# Top_Level.net
KiCad netlist of a schematic drawn in Altium Designer
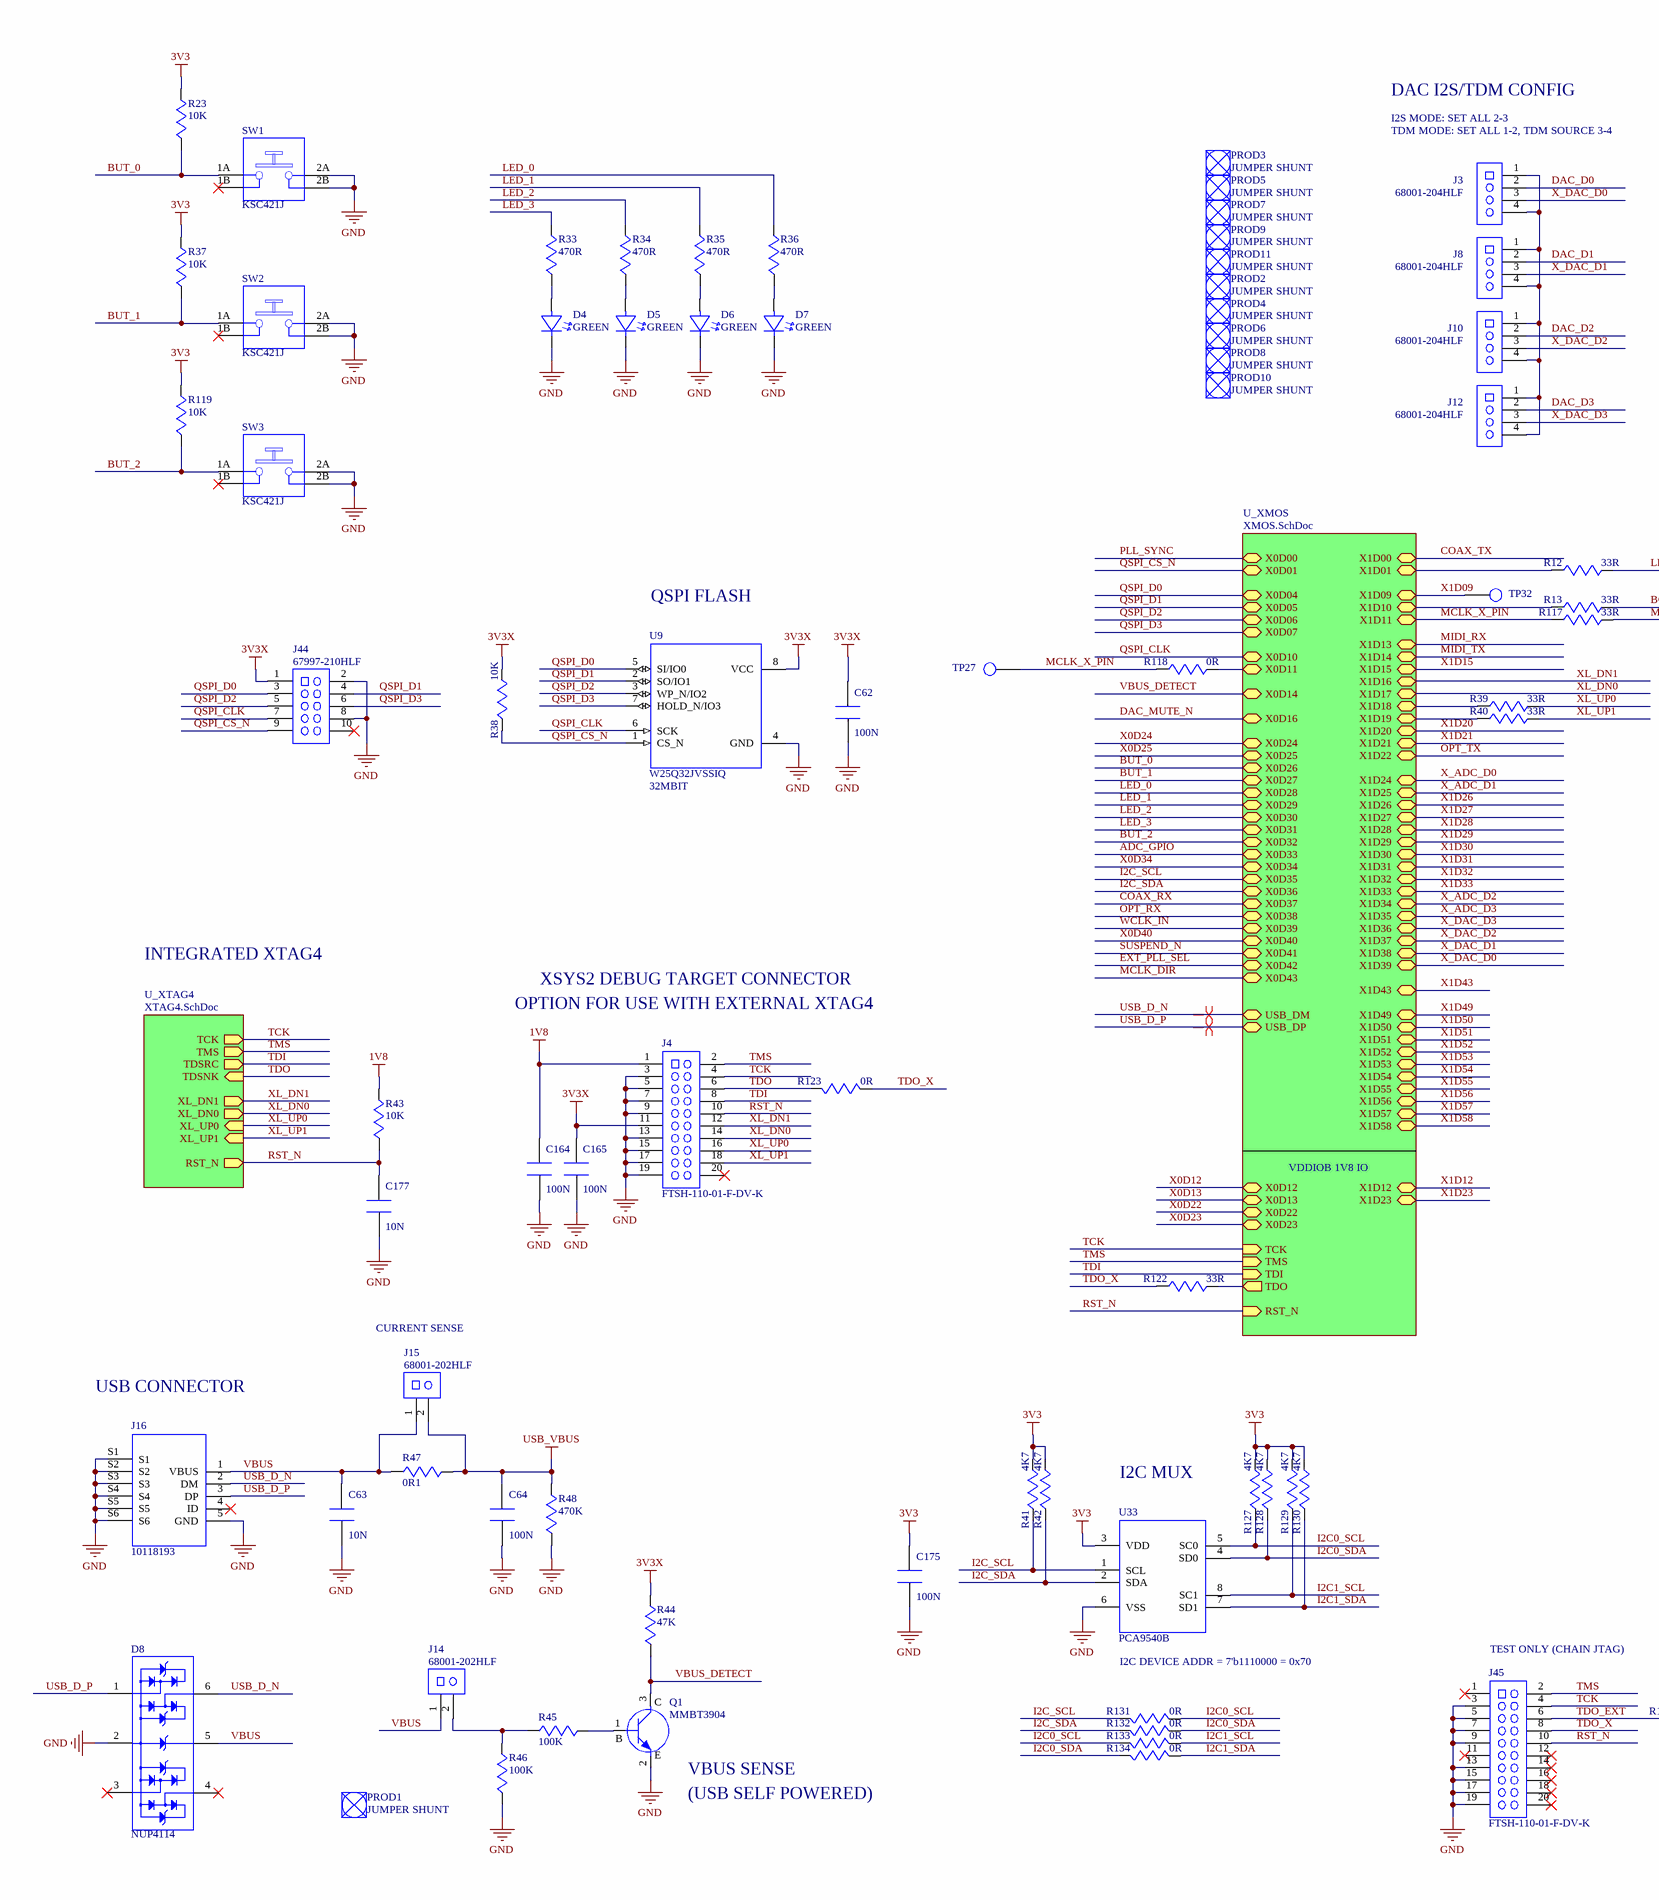
[diagram p0: Top Level.SchDoc, left]
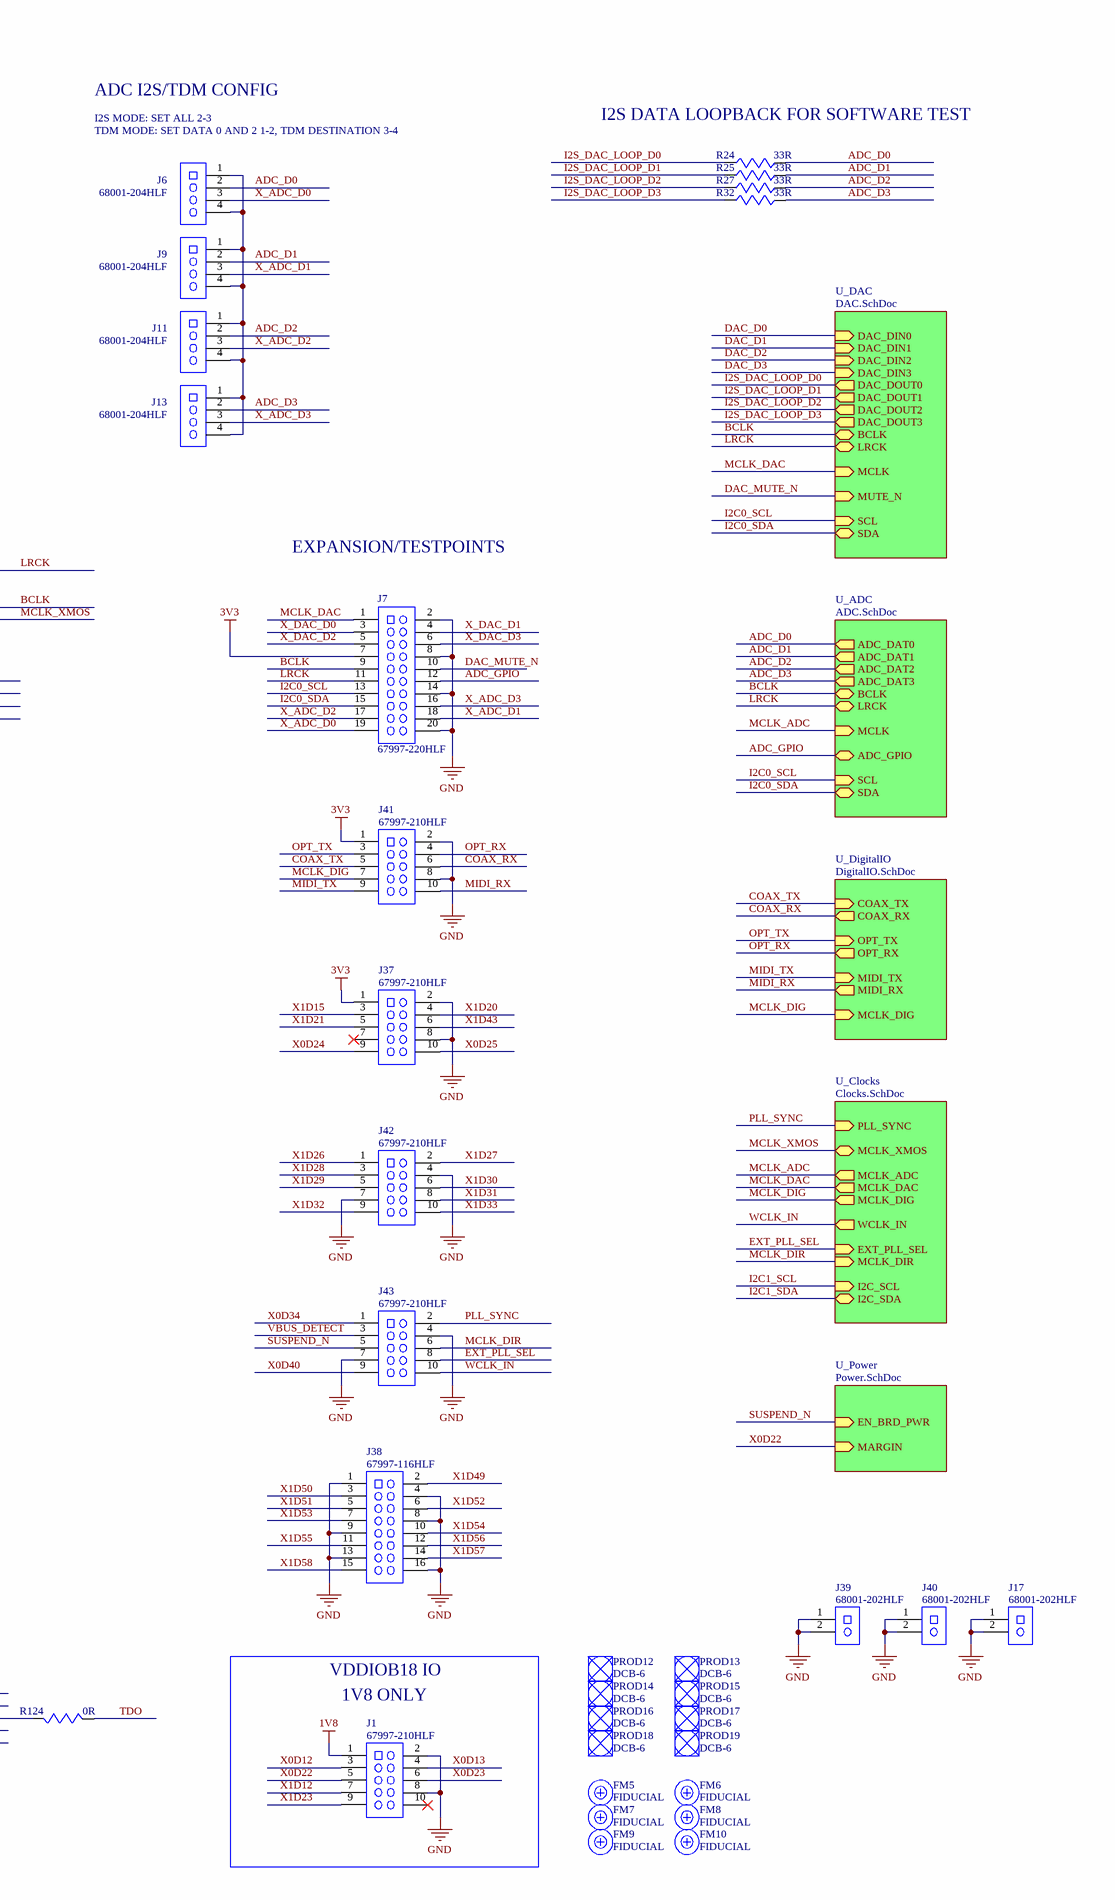
[diagram p1: Top Level.SchDoc, right]

(export (version "E")
  (design (tool "Eeschema 10.0.6"))
  (components
    (comp (ref "C62")
      (value "100N")
      (footprint "CAPC1005X55N")
      (description "CHIP CAPACITOR, CERAMIC, 100NF, 16V, 10%, X7R, 0402")
      (fields (field (name "PART NUMBER") "STD-06-0048") (field (name "TOLERANCE") "10%"))
      (libsource (lib "JG_StandardLibrary") (part "CAP_NP"))
    )
    (comp (ref "C63")
      (value "10N")
      (footprint "CAPC1005X55N")
      (description "CHIP CAPACITOR, CERAMIC, 10NF, 50V, 10%, X7R, 0402")
      (fields (field (name "PART NUMBER") "STD-06-0042") (field (name "TOLERANCE") "10%"))
      (libsource (lib "JG_StandardLibrary") (part "CAP_NP"))
    )
    (comp (ref "C64")
      (value "100N")
      (footprint "CAPC1005X55N")
      (description "CHIP CAPACITOR, CERAMIC, 100NF, 16V, 10%, X7R, 0402")
      (fields (field (name "PART NUMBER") "STD-06-0048") (field (name "TOLERANCE") "10%"))
      (libsource (lib "JG_StandardLibrary") (part "CAP_NP"))
    )
    (comp (ref "C164")
      (value "100N")
      (footprint "CAPC1005X55N")
      (description "CHIP CAPACITOR, CERAMIC, 100NF, 16V, 10%, X7R, 0402")
      (fields (field (name "PART NUMBER") "STD-06-0048") (field (name "TOLERANCE") "10%"))
      (libsource (lib "JG_StandardLibrary") (part "CAP_NP"))
    )
    (comp (ref "C165")
      (value "100N")
      (footprint "CAPC1005X55N")
      (description "CHIP CAPACITOR, CERAMIC, 100NF, 16V, 10%, X7R, 0402")
      (fields (field (name "PART NUMBER") "STD-06-0048") (field (name "TOLERANCE") "10%"))
      (libsource (lib "JG_StandardLibrary") (part "CAP_NP"))
    )
    (comp (ref "C175")
      (value "100N")
      (footprint "CAPC1005X55N")
      (description "CHIP CAPACITOR, CERAMIC, 100NF, 16V, 10%, X7R, 0402")
      (fields (field (name "PART NUMBER") "STD-06-0048") (field (name "TOLERANCE") "10%"))
      (libsource (lib "JG_StandardLibrary") (part "CAP_NP"))
    )
    (comp (ref "C177")
      (value "10N")
      (footprint "CAPC1005X55N")
      (description "CHIP CAPACITOR, CERAMIC, 10NF, 50V, 10%, X7R, 0402")
      (fields (field (name "PART NUMBER") "STD-06-0042") (field (name "TOLERANCE") "10%"))
      (libsource (lib "JG_StandardLibrary") (part "CAP_NP"))
    )
    (comp (ref "D4")
      (value "APT1608")
      (footprint "LEDC1608X85N")
      (description "LED, GREEN, 0603")
      (fields
        (field (name "PART NUMBER") "GEN-17-0001")
        (field (name "COLOUR") "GREEN")
        (field (name "MANUFACTURER") "Kingbright")
      )
      (libsource (lib "JG_GeneralLibrary") (part "LED"))
    )
    (comp (ref "D5")
      (value "APT1608")
      (footprint "LEDC1608X85N")
      (description "LED, GREEN, 0603")
      (fields
        (field (name "PART NUMBER") "GEN-17-0001")
        (field (name "COLOUR") "GREEN")
        (field (name "MANUFACTURER") "Kingbright")
      )
      (libsource (lib "JG_GeneralLibrary") (part "LED"))
    )
    (comp (ref "D6")
      (value "APT1608")
      (footprint "LEDC1608X85N")
      (description "LED, GREEN, 0603")
      (fields
        (field (name "PART NUMBER") "GEN-17-0001")
        (field (name "COLOUR") "GREEN")
        (field (name "MANUFACTURER") "Kingbright")
      )
      (libsource (lib "JG_GeneralLibrary") (part "LED"))
    )
    (comp (ref "D7")
      (value "APT1608")
      (footprint "LEDC1608X85N")
      (description "LED, GREEN, 0603")
      (fields
        (field (name "PART NUMBER") "GEN-17-0001")
        (field (name "COLOUR") "GREEN")
        (field (name "MANUFACTURER") "Kingbright")
      )
      (libsource (lib "JG_GeneralLibrary") (part "LED"))
    )
    (comp (ref "D8")
      (value "NUP4114")
      (footprint "SOT65P210X110-6N")
      (description "ESD Protection Diode Array, 0.6pF, SC-70-6 (SC-88)")
      (fields (field (name "PART NUMBER") "GEN-16-0048") (field (name "MANUFACTURER") "ON Semiconductor"))
      (libsource (lib "JG_GeneralLibrary") (part "DIODE_QUAD_ESD_C"))
    )
    (comp (ref "FM5")
      (value "FIDUCIAL")
      (footprint "FIDUCIAL_10_20")
      (description "Fiducial, Circle, 1mm Pad, 2mm Keepout")
      (fields (field (name "PART NUMBER") "GEN-24-0001") (field (name "MANUFACTURER") "NA"))
      (libsource (lib "JG_GeneralLibrary") (part "FIDUCIAL"))
    )
    (comp (ref "FM6")
      (value "FIDUCIAL")
      (footprint "FIDUCIAL_10_20")
      (description "Fiducial, Circle, 1mm Pad, 2mm Keepout")
      (fields (field (name "PART NUMBER") "GEN-24-0001") (field (name "MANUFACTURER") "NA"))
      (libsource (lib "JG_GeneralLibrary") (part "FIDUCIAL"))
    )
    (comp (ref "FM7")
      (value "FIDUCIAL")
      (footprint "FIDUCIAL_10_20")
      (description "Fiducial, Circle, 1mm Pad, 2mm Keepout")
      (fields (field (name "PART NUMBER") "GEN-24-0001") (field (name "MANUFACTURER") "NA"))
      (libsource (lib "JG_GeneralLibrary") (part "FIDUCIAL"))
    )
    (comp (ref "FM8")
      (value "FIDUCIAL")
      (footprint "FIDUCIAL_10_20")
      (description "Fiducial, Circle, 1mm Pad, 2mm Keepout")
      (fields (field (name "PART NUMBER") "GEN-24-0001") (field (name "MANUFACTURER") "NA"))
      (libsource (lib "JG_GeneralLibrary") (part "FIDUCIAL"))
    )
    (comp (ref "FM9")
      (value "FIDUCIAL")
      (footprint "FIDUCIAL_10_20")
      (description "Fiducial, Circle, 1mm Pad, 2mm Keepout")
      (fields (field (name "PART NUMBER") "GEN-24-0001") (field (name "MANUFACTURER") "NA"))
      (libsource (lib "JG_GeneralLibrary") (part "FIDUCIAL"))
    )
    (comp (ref "FM10")
      (value "FIDUCIAL")
      (footprint "FIDUCIAL_10_20")
      (description "Fiducial, Circle, 1mm Pad, 2mm Keepout")
      (fields (field (name "PART NUMBER") "GEN-24-0001") (field (name "MANUFACTURER") "NA"))
      (libsource (lib "JG_GeneralLibrary") (part "FIDUCIAL"))
    )
    (comp (ref "J1")
      (value "67997-210HLF")
      (footprint "HDR_FCI_67997_X10")
      (description "Pin Header, Male, Vertical, Through Hole, 10 Way, 2x5, 0.1 Inch Pitch")
      (fields (field (name "PART NUMBER") "GEN-01-0029") (field (name "MANUFACTURER") "FCI"))
      (libsource (lib "JG_GeneralLibrary") (part "IDC_HEADER_10"))
    )
    (comp (ref "J3")
      (value "68001-204HLF")
      (footprint "HDR_FCI_68001_204")
      (description "Pin Header, Male, Vertical, Through Hole, 4 Way, 1x4, 0.1 Inch Pitch")
      (fields (field (name "PART NUMBER") "GEN-01-0125") (field (name "MANUFACTURER") "FCI"))
      (libsource (lib "JG_GeneralLibrary") (part "PIN_HEADER_1X4"))
    )
    (comp (ref "J4")
      (value "FTSH-110-01-F-DV-K")
      (footprint "CON_SAMTEC_FTSH_110_01_X_DV_K")
      (description "Pin Header, Male, Vertical, 20 Way, 2x10, 1.27mm Pitch, Keying Shroud, SMD")
      (fields (field (name "PART NUMBER") "GEN-01-0126") (field (name "MANUFACTURER") "Samtec"))
      (libsource (lib "JG_GeneralLibrary") (part "IDC_HEADER_20"))
    )
    (comp (ref "J6")
      (value "68001-204HLF")
      (footprint "HDR_FCI_68001_204")
      (description "Pin Header, Male, Vertical, Through Hole, 4 Way, 1x4, 0.1 Inch Pitch")
      (fields (field (name "PART NUMBER") "GEN-01-0125") (field (name "MANUFACTURER") "FCI"))
      (libsource (lib "JG_GeneralLibrary") (part "PIN_HEADER_1X4"))
    )
    (comp (ref "J7")
      (value "67997-220HLF")
      (footprint "HDR_FCI_67997_220")
      (description "Pin Header, Male, Vertical, Through Hole, 20 Way, 2x10, 0.1 Inch Pitch")
      (fields (field (name "PART NUMBER") "GEN-01-0070") (field (name "MANUFACTURER") "FCI"))
      (libsource (lib "JG_GeneralLibrary") (part "IDC_HEADER_20"))
    )
    (comp (ref "J8")
      (value "68001-204HLF")
      (footprint "HDR_FCI_68001_204")
      (description "Pin Header, Male, Vertical, Through Hole, 4 Way, 1x4, 0.1 Inch Pitch")
      (fields (field (name "PART NUMBER") "GEN-01-0125") (field (name "MANUFACTURER") "FCI"))
      (libsource (lib "JG_GeneralLibrary") (part "PIN_HEADER_1X4"))
    )
    (comp (ref "J9")
      (value "68001-204HLF")
      (footprint "HDR_FCI_68001_204")
      (description "Pin Header, Male, Vertical, Through Hole, 4 Way, 1x4, 0.1 Inch Pitch")
      (fields (field (name "PART NUMBER") "GEN-01-0125") (field (name "MANUFACTURER") "FCI"))
      (libsource (lib "JG_GeneralLibrary") (part "PIN_HEADER_1X4"))
    )
    (comp (ref "J10")
      (value "68001-204HLF")
      (footprint "HDR_FCI_68001_204")
      (description "Pin Header, Male, Vertical, Through Hole, 4 Way, 1x4, 0.1 Inch Pitch")
      (fields (field (name "PART NUMBER") "GEN-01-0125") (field (name "MANUFACTURER") "FCI"))
      (libsource (lib "JG_GeneralLibrary") (part "PIN_HEADER_1X4"))
    )
    (comp (ref "J11")
      (value "68001-204HLF")
      (footprint "HDR_FCI_68001_204")
      (description "Pin Header, Male, Vertical, Through Hole, 4 Way, 1x4, 0.1 Inch Pitch")
      (fields (field (name "PART NUMBER") "GEN-01-0125") (field (name "MANUFACTURER") "FCI"))
      (libsource (lib "JG_GeneralLibrary") (part "PIN_HEADER_1X4"))
    )
    (comp (ref "J12")
      (value "68001-204HLF")
      (footprint "HDR_FCI_68001_204")
      (description "Pin Header, Male, Vertical, Through Hole, 4 Way, 1x4, 0.1 Inch Pitch")
      (fields (field (name "PART NUMBER") "GEN-01-0125") (field (name "MANUFACTURER") "FCI"))
      (libsource (lib "JG_GeneralLibrary") (part "PIN_HEADER_1X4"))
    )
    (comp (ref "J13")
      (value "68001-204HLF")
      (footprint "HDR_FCI_68001_204")
      (description "Pin Header, Male, Vertical, Through Hole, 4 Way, 1x4, 0.1 Inch Pitch")
      (fields (field (name "PART NUMBER") "GEN-01-0125") (field (name "MANUFACTURER") "FCI"))
      (libsource (lib "JG_GeneralLibrary") (part "PIN_HEADER_1X4"))
    )
    (comp (ref "J14")
      (value "68001-202HLF")
      (footprint "HDR_FCI_68001_202")
      (description "Pin Header, Male, Vertical, Through Hole, 2 Way, 1x2, 0.1 Inch Pitch")
      (fields (field (name "PART NUMBER") "GEN-01-0011") (field (name "MANUFACTURER") "FCI"))
      (libsource (lib "JG_GeneralLibrary") (part "PIN_HEADER_1X2"))
    )
    (comp (ref "J15")
      (value "68001-202HLF")
      (footprint "HDR_FCI_68001_202")
      (description "Pin Header, Male, Vertical, Through Hole, 2 Way, 1x2, 0.1 Inch Pitch")
      (fields (field (name "PART NUMBER") "GEN-01-0011") (field (name "MANUFACTURER") "FCI"))
      (libsource (lib "JG_GeneralLibrary") (part "PIN_HEADER_1X2"))
    )
    (comp (ref "J16")
      (value "10118193")
      (footprint "CON_FCI_10118193")
      (description "USB Micro B Receptacle, Right Angle, SMD w/2 DIP Legs")
      (fields (field (name "PART NUMBER") "GEN-01-0020") (field (name "MANUFACTURER") "FCI"))
      (libsource (lib "JG_GeneralLibrary") (part "FCI_10118193"))
    )
    (comp (ref "J17")
      (value "68001-202HLF")
      (footprint "HDR_FCI_68001_202")
      (description "Pin Header, Male, Vertical, Through Hole, 2 Way, 1x2, 0.1 Inch Pitch")
      (fields (field (name "PART NUMBER") "GEN-01-0011") (field (name "MANUFACTURER") "FCI"))
      (libsource (lib "JG_GeneralLibrary") (part "PIN_HEADER_1X2"))
    )
    (comp (ref "J37")
      (value "67997-210HLF")
      (footprint "HDR_FCI_67997_X10")
      (description "Pin Header, Male, Vertical, Through Hole, 10 Way, 2x5, 0.1 Inch Pitch")
      (fields (field (name "PART NUMBER") "GEN-01-0029") (field (name "MANUFACTURER") "FCI"))
      (libsource (lib "JG_GeneralLibrary") (part "IDC_HEADER_10"))
    )
    (comp (ref "J38")
      (value "67997-116HLF")
      (footprint "HDR_FCI_67997_116")
      (description "Pin Header, Male, Through Hole, 16 Way, 2x8, 0.76u Gold, 0.1 Inch Pitch")
      (fields (field (name "PART NUMBER") "GEN-01-0019") (field (name "MANUFACTURER") "FCI"))
      (libsource (lib "JG_GeneralLibrary") (part "IDC_HEADER_16"))
    )
    (comp (ref "J39")
      (value "68001-202HLF")
      (footprint "HDR_FCI_68001_202")
      (description "Pin Header, Male, Vertical, Through Hole, 2 Way, 1x2, 0.1 Inch Pitch")
      (fields (field (name "PART NUMBER") "GEN-01-0011") (field (name "MANUFACTURER") "FCI"))
      (libsource (lib "JG_GeneralLibrary") (part "PIN_HEADER_1X2"))
    )
    (comp (ref "J40")
      (value "68001-202HLF")
      (footprint "HDR_FCI_68001_202")
      (description "Pin Header, Male, Vertical, Through Hole, 2 Way, 1x2, 0.1 Inch Pitch")
      (fields (field (name "PART NUMBER") "GEN-01-0011") (field (name "MANUFACTURER") "FCI"))
      (libsource (lib "JG_GeneralLibrary") (part "PIN_HEADER_1X2"))
    )
    (comp (ref "J41")
      (value "67997-210HLF")
      (footprint "HDR_FCI_67997_X10")
      (description "Pin Header, Male, Vertical, Through Hole, 10 Way, 2x5, 0.1 Inch Pitch")
      (fields (field (name "PART NUMBER") "GEN-01-0029") (field (name "MANUFACTURER") "FCI"))
      (libsource (lib "JG_GeneralLibrary") (part "IDC_HEADER_10"))
    )
    (comp (ref "J42")
      (value "67997-210HLF")
      (footprint "HDR_FCI_67997_X10")
      (description "Pin Header, Male, Vertical, Through Hole, 10 Way, 2x5, 0.1 Inch Pitch")
      (fields (field (name "PART NUMBER") "GEN-01-0029") (field (name "MANUFACTURER") "FCI"))
      (libsource (lib "JG_GeneralLibrary") (part "IDC_HEADER_10"))
    )
    (comp (ref "J43")
      (value "67997-210HLF")
      (footprint "HDR_FCI_67997_X10")
      (description "Pin Header, Male, Vertical, Through Hole, 10 Way, 2x5, 0.1 Inch Pitch")
      (fields (field (name "PART NUMBER") "GEN-01-0029") (field (name "MANUFACTURER") "FCI"))
      (libsource (lib "JG_GeneralLibrary") (part "IDC_HEADER_10"))
    )
    (comp (ref "J44")
      (value "67997-210HLF")
      (footprint "HDR_FCI_67997_X10")
      (description "Pin Header, Male, Vertical, Through Hole, 10 Way, 2x5, 0.1 Inch Pitch")
      (fields (field (name "PART NUMBER") "GEN-01-0029") (field (name "MANUFACTURER") "FCI"))
      (libsource (lib "JG_GeneralLibrary") (part "IDC_HEADER_10"))
    )
    (comp (ref "J45")
      (value "FTSH-110-01-F-DV-K")
      (footprint "CON_SAMTEC_FTSH_110_01_X_DV_K")
      (description "Pin Header, Male, Vertical, 20 Way, 2x10, 1.27mm Pitch, Keying Shroud, SMD")
      (fields (field (name "PART NUMBER") "GEN-01-0126") (field (name "MANUFACTURER") "Samtec"))
      (libsource (lib "JG_GeneralLibrary") (part "IDC_HEADER_20"))
    )
    (comp (ref "PROD1")
      (value "JUMPER SHUNT")
      (description "Jumper Shunt, Single Circuit, Open Type, 2.54mm Pitch, 6mm High, Gold Flash")
      (fields (field (name "PART NUMBER") "GEN-23-0011") (field (name "MANUFACTURER") "Sullins"))
      (libsource (lib "JG_GeneralLibrary") (part "PROD_ITEM"))
    )
    (comp (ref "PROD2")
      (value "JUMPER SHUNT")
      (description "Jumper Shunt, Single Circuit, Open Type, 2.54mm Pitch, 6mm High, Gold Flash")
      (fields (field (name "PART NUMBER") "GEN-23-0011") (field (name "MANUFACTURER") "Sullins"))
      (libsource (lib "JG_GeneralLibrary") (part "PROD_ITEM"))
    )
    (comp (ref "PROD3")
      (value "JUMPER SHUNT")
      (description "Jumper Shunt, Single Circuit, Open Type, 2.54mm Pitch, 6mm High, Gold Flash")
      (fields (field (name "PART NUMBER") "GEN-23-0011") (field (name "MANUFACTURER") "Sullins"))
      (libsource (lib "JG_GeneralLibrary") (part "PROD_ITEM"))
    )
    (comp (ref "PROD4")
      (value "JUMPER SHUNT")
      (description "Jumper Shunt, Single Circuit, Open Type, 2.54mm Pitch, 6mm High, Gold Flash")
      (fields (field (name "PART NUMBER") "GEN-23-0011") (field (name "MANUFACTURER") "Sullins"))
      (libsource (lib "JG_GeneralLibrary") (part "PROD_ITEM"))
    )
    (comp (ref "PROD5")
      (value "JUMPER SHUNT")
      (description "Jumper Shunt, Single Circuit, Open Type, 2.54mm Pitch, 6mm High, Gold Flash")
      (fields (field (name "PART NUMBER") "GEN-23-0011") (field (name "MANUFACTURER") "Sullins"))
      (libsource (lib "JG_GeneralLibrary") (part "PROD_ITEM"))
    )
    (comp (ref "PROD6")
      (value "JUMPER SHUNT")
      (description "Jumper Shunt, Single Circuit, Open Type, 2.54mm Pitch, 6mm High, Gold Flash")
      (fields (field (name "PART NUMBER") "GEN-23-0011") (field (name "MANUFACTURER") "Sullins"))
      (libsource (lib "JG_GeneralLibrary") (part "PROD_ITEM"))
    )
    (comp (ref "PROD7")
      (value "JUMPER SHUNT")
      (description "Jumper Shunt, Single Circuit, Open Type, 2.54mm Pitch, 6mm High, Gold Flash")
      (fields (field (name "PART NUMBER") "GEN-23-0011") (field (name "MANUFACTURER") "Sullins"))
      (libsource (lib "JG_GeneralLibrary") (part "PROD_ITEM"))
    )
    (comp (ref "PROD8")
      (value "JUMPER SHUNT")
      (description "Jumper Shunt, Single Circuit, Open Type, 2.54mm Pitch, 6mm High, Gold Flash")
      (fields (field (name "PART NUMBER") "GEN-23-0011") (field (name "MANUFACTURER") "Sullins"))
      (libsource (lib "JG_GeneralLibrary") (part "PROD_ITEM"))
    )
    (comp (ref "PROD9")
      (value "JUMPER SHUNT")
      (description "Jumper Shunt, Single Circuit, Open Type, 2.54mm Pitch, 6mm High, Gold Flash")
      (fields (field (name "PART NUMBER") "GEN-23-0011") (field (name "MANUFACTURER") "Sullins"))
      (libsource (lib "JG_GeneralLibrary") (part "PROD_ITEM"))
    )
    (comp (ref "PROD10")
      (value "JUMPER SHUNT")
      (description "Jumper Shunt, Single Circuit, Open Type, 2.54mm Pitch, 6mm High, Gold Flash")
      (fields (field (name "PART NUMBER") "GEN-23-0011") (field (name "MANUFACTURER") "Sullins"))
      (libsource (lib "JG_GeneralLibrary") (part "PROD_ITEM"))
    )
    (comp (ref "PROD11")
      (value "JUMPER SHUNT")
      (description "Jumper Shunt, Single Circuit, Open Type, 2.54mm Pitch, 6mm High, Gold Flash")
      (fields (field (name "PART NUMBER") "GEN-23-0011") (field (name "MANUFACTURER") "Sullins"))
      (libsource (lib "JG_GeneralLibrary") (part "PROD_ITEM"))
    )
    (comp (ref "PROD12")
      (value "DCB-6")
      (description "Snap-in PCB Spacer Support, 6mm")
      (fields
        (field (name "PART NUMBER") "GEN-23-0002")
        (field (name "MANUFACTURER") "KANG YANG (Toby Electronics)")
      )
      (libsource (lib "JG_GeneralLibrary") (part "PROD_ITEM"))
    )
    (comp (ref "PROD13")
      (value "DCB-6")
      (description "Snap-in PCB Spacer Support, 6mm")
      (fields
        (field (name "PART NUMBER") "GEN-23-0002")
        (field (name "MANUFACTURER") "KANG YANG (Toby Electronics)")
      )
      (libsource (lib "JG_GeneralLibrary") (part "PROD_ITEM"))
    )
    (comp (ref "PROD14")
      (value "DCB-6")
      (description "Snap-in PCB Spacer Support, 6mm")
      (fields
        (field (name "PART NUMBER") "GEN-23-0002")
        (field (name "MANUFACTURER") "KANG YANG (Toby Electronics)")
      )
      (libsource (lib "JG_GeneralLibrary") (part "PROD_ITEM"))
    )
    (comp (ref "PROD15")
      (value "DCB-6")
      (description "Snap-in PCB Spacer Support, 6mm")
      (fields
        (field (name "PART NUMBER") "GEN-23-0002")
        (field (name "MANUFACTURER") "KANG YANG (Toby Electronics)")
      )
      (libsource (lib "JG_GeneralLibrary") (part "PROD_ITEM"))
    )
    (comp (ref "PROD16")
      (value "DCB-6")
      (description "Snap-in PCB Spacer Support, 6mm")
      (fields
        (field (name "PART NUMBER") "GEN-23-0002")
        (field (name "MANUFACTURER") "KANG YANG (Toby Electronics)")
      )
      (libsource (lib "JG_GeneralLibrary") (part "PROD_ITEM"))
    )
    (comp (ref "PROD17")
      (value "DCB-6")
      (description "Snap-in PCB Spacer Support, 6mm")
      (fields
        (field (name "PART NUMBER") "GEN-23-0002")
        (field (name "MANUFACTURER") "KANG YANG (Toby Electronics)")
      )
      (libsource (lib "JG_GeneralLibrary") (part "PROD_ITEM"))
    )
    (comp (ref "PROD18")
      (value "DCB-6")
      (description "Snap-in PCB Spacer Support, 6mm")
      (fields
        (field (name "PART NUMBER") "GEN-23-0002")
        (field (name "MANUFACTURER") "KANG YANG (Toby Electronics)")
      )
      (libsource (lib "JG_GeneralLibrary") (part "PROD_ITEM"))
    )
    (comp (ref "PROD19")
      (value "DCB-6")
      (description "Snap-in PCB Spacer Support, 6mm")
      (fields
        (field (name "PART NUMBER") "GEN-23-0002")
        (field (name "MANUFACTURER") "KANG YANG (Toby Electronics)")
      )
      (libsource (lib "JG_GeneralLibrary") (part "PROD_ITEM"))
    )
    (comp (ref "Q1")
      (value "MMBT3904")
      (footprint "SOT95P235X115-3N")
      (description "BJT Transistor, NPN, 40V, 200mA, SOT23")
      (fields (field (name "PART NUMBER") "GEN-16-0051") (field (name "MANUFACTURER") "Nexperia"))
      (libsource (lib "JG_GeneralLibrary") (part "NPN_3_A"))
    )
    (comp (ref "R12")
      (value "33R")
      (footprint "RESC1608X55N")
      (description "CHIP RESISTOR, 33 OHM, 0.1W, 1%, 0603")
      (fields (field (name "PART NUMBER") "STD-02-0026") (field (name "TOLERANCE") "1%"))
      (libsource (lib "JG_StandardLibrary") (part "RES"))
    )
    (comp (ref "R13")
      (value "33R")
      (footprint "RESC1608X55N")
      (description "CHIP RESISTOR, 33 OHM, 0.1W, 1%, 0603")
      (fields (field (name "PART NUMBER") "STD-02-0026") (field (name "TOLERANCE") "1%"))
      (libsource (lib "JG_StandardLibrary") (part "RES"))
    )
    (comp (ref "R23")
      (value "10K")
      (footprint "RESC1608X55N")
      (description "CHIP RESISTOR, 10K OHM, 0.1W, 1%, 0603")
      (fields (field (name "PART NUMBER") "STD-02-0086") (field (name "TOLERANCE") "1%"))
      (libsource (lib "JG_StandardLibrary") (part "RES"))
    )
    (comp (ref "R24")
      (value "33R")
      (footprint "RESC1608X55N")
      (description "CHIP RESISTOR, 33 OHM, 0.1W, 1%, 0603")
      (fields (field (name "PART NUMBER") "STD-02-0026") (field (name "TOLERANCE") "1%"))
      (libsource (lib "JG_StandardLibrary") (part "RES"))
    )
    (comp (ref "R25")
      (value "33R")
      (footprint "RESC1608X55N")
      (description "CHIP RESISTOR, 33 OHM, 0.1W, 1%, 0603")
      (fields (field (name "PART NUMBER") "STD-02-0026") (field (name "TOLERANCE") "1%"))
      (libsource (lib "JG_StandardLibrary") (part "RES"))
    )
    (comp (ref "R27")
      (value "33R")
      (footprint "RESC1608X55N")
      (description "CHIP RESISTOR, 33 OHM, 0.1W, 1%, 0603")
      (fields (field (name "PART NUMBER") "STD-02-0026") (field (name "TOLERANCE") "1%"))
      (libsource (lib "JG_StandardLibrary") (part "RES"))
    )
    (comp (ref "R32")
      (value "33R")
      (footprint "RESC1608X55N")
      (description "CHIP RESISTOR, 33 OHM, 0.1W, 1%, 0603")
      (fields (field (name "PART NUMBER") "STD-02-0026") (field (name "TOLERANCE") "1%"))
      (libsource (lib "JG_StandardLibrary") (part "RES"))
    )
    (comp (ref "R33")
      (value "470R")
      (footprint "RESC1608X55N")
      (description "CHIP RESISTOR, 470 OHM, 0.1W, 1%, 0603")
      (fields (field (name "PART NUMBER") "STD-02-0054") (field (name "TOLERANCE") "1%"))
      (libsource (lib "JG_StandardLibrary") (part "RES"))
    )
    (comp (ref "R34")
      (value "470R")
      (footprint "RESC1608X55N")
      (description "CHIP RESISTOR, 470 OHM, 0.1W, 1%, 0603")
      (fields (field (name "PART NUMBER") "STD-02-0054") (field (name "TOLERANCE") "1%"))
      (libsource (lib "JG_StandardLibrary") (part "RES"))
    )
    (comp (ref "R35")
      (value "470R")
      (footprint "RESC1608X55N")
      (description "CHIP RESISTOR, 470 OHM, 0.1W, 1%, 0603")
      (fields (field (name "PART NUMBER") "STD-02-0054") (field (name "TOLERANCE") "1%"))
      (libsource (lib "JG_StandardLibrary") (part "RES"))
    )
    (comp (ref "R36")
      (value "470R")
      (footprint "RESC1608X55N")
      (description "CHIP RESISTOR, 470 OHM, 0.1W, 1%, 0603")
      (fields (field (name "PART NUMBER") "STD-02-0054") (field (name "TOLERANCE") "1%"))
      (libsource (lib "JG_StandardLibrary") (part "RES"))
    )
    (comp (ref "R37")
      (value "10K")
      (footprint "RESC1608X55N")
      (description "CHIP RESISTOR, 10K OHM, 0.1W, 1%, 0603")
      (fields (field (name "PART NUMBER") "STD-02-0086") (field (name "TOLERANCE") "1%"))
      (libsource (lib "JG_StandardLibrary") (part "RES"))
    )
    (comp (ref "R38")
      (value "10K")
      (footprint "RESC1608X55N")
      (description "CHIP RESISTOR, 10K OHM, 0.1W, 1%, 0603")
      (fields (field (name "PART NUMBER") "STD-02-0086") (field (name "TOLERANCE") "1%"))
      (libsource (lib "JG_StandardLibrary") (part "RES"))
    )
    (comp (ref "R39")
      (value "33R")
      (footprint "RESC1608X55N")
      (description "CHIP RESISTOR, 33 OHM, 0.1W, 1%, 0603")
      (fields (field (name "PART NUMBER") "STD-02-0026") (field (name "TOLERANCE") "1%"))
      (libsource (lib "JG_StandardLibrary") (part "RES"))
    )
    (comp (ref "R40")
      (value "33R")
      (footprint "RESC1608X55N")
      (description "CHIP RESISTOR, 33 OHM, 0.1W, 1%, 0603")
      (fields (field (name "PART NUMBER") "STD-02-0026") (field (name "TOLERANCE") "1%"))
      (libsource (lib "JG_StandardLibrary") (part "RES"))
    )
    (comp (ref "R41")
      (value "4K7")
      (footprint "RESC1608X55N")
      (description "CHIP RESISTOR, 4.7K OHM, 0.1W, 1%, 0603")
      (fields (field (name "PART NUMBER") "STD-02-0078") (field (name "TOLERANCE") "1%"))
      (libsource (lib "JG_StandardLibrary") (part "RES"))
    )
    (comp (ref "R42")
      (value "4K7")
      (footprint "RESC1608X55N")
      (description "CHIP RESISTOR, 4.7K OHM, 0.1W, 1%, 0603")
      (fields (field (name "PART NUMBER") "STD-02-0078") (field (name "TOLERANCE") "1%"))
      (libsource (lib "JG_StandardLibrary") (part "RES"))
    )
    (comp (ref "R43")
      (value "10K")
      (footprint "RESC1608X55N")
      (description "CHIP RESISTOR, 10K OHM, 0.1W, 1%, 0603")
      (fields (field (name "PART NUMBER") "STD-02-0086") (field (name "TOLERANCE") "1%"))
      (libsource (lib "JG_StandardLibrary") (part "RES"))
    )
    (comp (ref "R44")
      (value "47K")
      (footprint "RESC1608X55N")
      (description "CHIP RESISTOR, 47K OHM, 0.1W, 1%, 0603")
      (fields (field (name "PART NUMBER") "STD-02-0102") (field (name "TOLERANCE") "1%"))
      (libsource (lib "JG_StandardLibrary") (part "RES"))
    )
    (comp (ref "R45")
      (value "100K")
      (footprint "RESC1608X55N")
      (description "CHIP RESISTOR, 100K OHM, 0.1W, 1%, 0603")
      (fields (field (name "PART NUMBER") "STD-02-0110") (field (name "TOLERANCE") "1%"))
      (libsource (lib "JG_StandardLibrary") (part "RES"))
    )
    (comp (ref "R46")
      (value "100K")
      (footprint "RESC1608X55N")
      (description "CHIP RESISTOR, 100K OHM, 0.1W, 1%, 0603")
      (fields (field (name "PART NUMBER") "STD-02-0110") (field (name "TOLERANCE") "1%"))
      (libsource (lib "JG_StandardLibrary") (part "RES"))
    )
    (comp (ref "R47")
      (value "0R1")
      (footprint "RESC2012X60N")
      (description "CHIP RESISTOR, 0.1 OHM, 250mW, 1%, 0805")
      (fields (field (name "PART NUMBER") "GEN-02-0029") (field (name "TOLERANCE") "1%"))
      (libsource (lib "JG_GeneralLibrary") (part "RES"))
    )
    (comp (ref "R48")
      (value "470K")
      (footprint "RESC1608X55N")
      (description "CHIP RESISTOR, 470K OHM, 0.1W, 1%, 0603")
      (fields (field (name "PART NUMBER") "STD-02-0126") (field (name "TOLERANCE") "1%"))
      (libsource (lib "JG_StandardLibrary") (part "RES"))
    )
    (comp (ref "R117")
      (value "33R")
      (footprint "RESC1608X55N")
      (description "CHIP RESISTOR, 33 OHM, 0.1W, 1%, 0603")
      (fields (field (name "PART NUMBER") "STD-02-0026") (field (name "TOLERANCE") "1%"))
      (libsource (lib "JG_StandardLibrary") (part "RES"))
    )
    (comp (ref "R118")
      (value "0R")
      (footprint "RESC1608X55N")
      (description "CHIP RESISTOR, ZERO OHM JUMPER, 1A, 0603")
      (fields (field (name "PART NUMBER") "STD-02-0001") (field (name "TOLERANCE") "NA"))
      (libsource (lib "JG_StandardLibrary") (part "RES"))
    )
    (comp (ref "R119")
      (value "10K")
      (footprint "RESC1608X55N")
      (description "CHIP RESISTOR, 10K OHM, 0.1W, 1%, 0603")
      (fields (field (name "PART NUMBER") "STD-02-0086") (field (name "TOLERANCE") "1%"))
      (libsource (lib "JG_StandardLibrary") (part "RES"))
    )
    (comp (ref "R122")
      (value "33R")
      (footprint "RESC1608X55N")
      (description "CHIP RESISTOR, 33 OHM, 0.1W, 1%, 0603")
      (fields (field (name "PART NUMBER") "STD-02-0026") (field (name "TOLERANCE") "1%"))
      (libsource (lib "JG_StandardLibrary") (part "RES"))
    )
    (comp (ref "R123")
      (value "0R")
      (footprint "RESC1608X55N")
      (description "CHIP RESISTOR, ZERO OHM JUMPER, 1A, 0603")
      (fields (field (name "PART NUMBER") "STD-02-0001") (field (name "TOLERANCE") "NA"))
      (libsource (lib "JG_StandardLibrary") (part "RES"))
    )
    (comp (ref "R124")
      (value "0R")
      (footprint "RESC1608X55N")
      (description "CHIP RESISTOR, ZERO OHM JUMPER, 1A, 0603")
      (fields (field (name "PART NUMBER") "STD-02-0001") (field (name "TOLERANCE") "NA"))
      (libsource (lib "JG_StandardLibrary") (part "RES"))
    )
    (comp (ref "R127")
      (value "4K7")
      (footprint "RESC1608X55N")
      (description "CHIP RESISTOR, 4.7K OHM, 0.1W, 1%, 0603")
      (fields (field (name "PART NUMBER") "STD-02-0078") (field (name "TOLERANCE") "1%"))
      (libsource (lib "JG_StandardLibrary") (part "RES"))
    )
    (comp (ref "R128")
      (value "4K7")
      (footprint "RESC1608X55N")
      (description "CHIP RESISTOR, 4.7K OHM, 0.1W, 1%, 0603")
      (fields (field (name "PART NUMBER") "STD-02-0078") (field (name "TOLERANCE") "1%"))
      (libsource (lib "JG_StandardLibrary") (part "RES"))
    )
    (comp (ref "R129")
      (value "4K7")
      (footprint "RESC1608X55N")
      (description "CHIP RESISTOR, 4.7K OHM, 0.1W, 1%, 0603")
      (fields (field (name "PART NUMBER") "STD-02-0078") (field (name "TOLERANCE") "1%"))
      (libsource (lib "JG_StandardLibrary") (part "RES"))
    )
    (comp (ref "R130")
      (value "4K7")
      (footprint "RESC1608X55N")
      (description "CHIP RESISTOR, 4.7K OHM, 0.1W, 1%, 0603")
      (fields (field (name "PART NUMBER") "STD-02-0078") (field (name "TOLERANCE") "1%"))
      (libsource (lib "JG_StandardLibrary") (part "RES"))
    )
    (comp (ref "R131")
      (value "0R")
      (footprint "RESC1608X55N")
      (description "CHIP RESISTOR, ZERO OHM JUMPER, 1A, 0603")
      (fields (field (name "PART NUMBER") "STD-02-0001") (field (name "TOLERANCE") "NA"))
      (libsource (lib "JG_StandardLibrary") (part "RES"))
    )
    (comp (ref "R132")
      (value "0R")
      (footprint "RESC1608X55N")
      (description "CHIP RESISTOR, ZERO OHM JUMPER, 1A, 0603")
      (fields (field (name "PART NUMBER") "STD-02-0001") (field (name "TOLERANCE") "NA"))
      (libsource (lib "JG_StandardLibrary") (part "RES"))
    )
    (comp (ref "R133")
      (value "0R")
      (footprint "RESC1608X55N")
      (description "CHIP RESISTOR, ZERO OHM JUMPER, 1A, 0603")
      (fields (field (name "PART NUMBER") "STD-02-0001") (field (name "TOLERANCE") "NA"))
      (libsource (lib "JG_StandardLibrary") (part "RES"))
    )
    (comp (ref "R134")
      (value "0R")
      (footprint "RESC1608X55N")
      (description "CHIP RESISTOR, ZERO OHM JUMPER, 1A, 0603")
      (fields (field (name "PART NUMBER") "STD-02-0001") (field (name "TOLERANCE") "NA"))
      (libsource (lib "JG_StandardLibrary") (part "RES"))
    )
    (comp (ref "SW1")
      (value "KSC421J")
      (footprint "SW_CK_KSC4_JBEND")
      (description "Tactile Switch, Momentary, J Bend SMD")
      (fields (field (name "PART NUMBER") "GEN-20-0004") (field (name "MANUFACTURER") "C&K"))
      (libsource (lib "JG_GeneralLibrary") (part "PB_SPST_A"))
    )
    (comp (ref "SW2")
      (value "KSC421J")
      (footprint "SW_CK_KSC4_JBEND")
      (description "Tactile Switch, Momentary, J Bend SMD")
      (fields (field (name "PART NUMBER") "GEN-20-0004") (field (name "MANUFACTURER") "C&K"))
      (libsource (lib "JG_GeneralLibrary") (part "PB_SPST_A"))
    )
    (comp (ref "SW3")
      (value "KSC421J")
      (footprint "SW_CK_KSC4_JBEND")
      (description "Tactile Switch, Momentary, J Bend SMD")
      (fields (field (name "PART NUMBER") "GEN-20-0004") (field (name "MANUFACTURER") "C&K"))
      (libsource (lib "JG_GeneralLibrary") (part "PB_SPST_A"))
    )
    (comp (ref "TP27")
      (value "TESTPOINT")
      (footprint "TESTPOINT_SMD_1MM")
      (description "Testpoint, SMD, 1mm")
      (fields (field (name "PART NUMBER") "GEN-24-0003") (field (name "MANUFACTURER") "NA"))
      (libsource (lib "JG_GeneralLibrary") (part "TESTPOINT"))
    )
    (comp (ref "TP32")
      (value "TESTPOINT")
      (footprint "TESTPOINT_SMD_0.9MM_L")
      (description "Testpoint, SMD, 0.9mm")
      (fields (field (name "PART NUMBER") "GEN-24-0019") (field (name "MANUFACTURER") "NA"))
      (libsource (lib "JG_GeneralLibrary") (part "TESTPOINT"))
    )
    (comp (ref "U9")
      (value "W25Q32JVSSIQ")
      (footprint "SOIC127P790X220-8N")
      (description "Memory, Flash, SPI, Multi-IO, 32Mb (16Kx256), 2.7 to 3.6V, QE = 1, SOIC-8-W")
      (fields
        (field (name "PART NUMBER") "GEN-12-0035")
        (field (name "MEMORY SIZE") "32MBIT")
        (field (name "MANUFACTURER") "Winbond")
      )
      (libsource (lib "JG_GeneralLibrary") (part "SPI_FLASH_MULTI_A"))
    )
    (comp (ref "U33")
      (value "PCA9540B")
      (footprint "SOP65P490X110-8N")
      (description "2-channel I2C-bus multiplexer, TSSOP8")
      (fields (field (name "PART NUMBER") "GEN-09-0030") (field (name "MANUFACTURER") "NXP"))
      (libsource (lib "JG_GeneralLibrary") (part "NXP_PCA9540B"))
    )
  )
  (nets
    (net (code "1") (name "/ADC_D0") (class "Default")
      (node (ref "J6") (pin "2") (pinfunction "2_2") (pintype "passive"))
      (node (ref "R24") (pin "2") (pinfunction "2_2") (pintype "passive"))
    )
    (net (code "2") (name "/ADC_D1") (class "Default")
      (node (ref "J9") (pin "2") (pinfunction "2_2") (pintype "passive"))
      (node (ref "R25") (pin "2") (pinfunction "2_2") (pintype "passive"))
    )
    (net (code "3") (name "/ADC_D2") (class "Default")
      (node (ref "J11") (pin "2") (pinfunction "2_2") (pintype "passive"))
      (node (ref "R27") (pin "2") (pinfunction "2_2") (pintype "passive"))
    )
    (net (code "4") (name "/ADC_D3") (class "Default")
      (node (ref "J13") (pin "2") (pinfunction "2_2") (pintype "passive"))
      (node (ref "R32") (pin "2") (pinfunction "2_2") (pintype "passive"))
    )
    (net (code "5") (name "/ADC_GPIO") (class "Default")
      (node (ref "J7") (pin "12") (pinfunction "12_12") (pintype "passive"))
    )
    (net (code "6") (name "/BCLK") (class "Default")
      (node (ref "J7") (pin "9") (pinfunction "9_9") (pintype "passive"))
      (node (ref "R13") (pin "2") (pinfunction "2_2") (pintype "passive"))
    )
    (net (code "7") (name "/BUT_0") (class "Default")
      (node (ref "R23") (pin "1") (pinfunction "1_1") (pintype "passive"))
      (node (ref "SW1") (pin "1A") (pinfunction "1A_1A") (pintype "passive"))
    )
    (net (code "8") (name "/BUT_1") (class "Default")
      (node (ref "R37") (pin "1") (pinfunction "1_1") (pintype "passive"))
      (node (ref "SW2") (pin "1A") (pinfunction "1A_1A") (pintype "passive"))
    )
    (net (code "9") (name "/BUT_2") (class "Default")
      (node (ref "R119") (pin "1") (pinfunction "1_1") (pintype "passive"))
      (node (ref "SW3") (pin "1A") (pinfunction "1A_1A") (pintype "passive"))
    )
    (net (code "10") (name "/COAX_RX") (class "Default")
      (node (ref "J41") (pin "6") (pinfunction "6_6") (pintype "passive"))
    )
    (net (code "11") (name "/COAX_TX") (class "Default")
      (node (ref "J41") (pin "5") (pinfunction "5_5") (pintype "passive"))
    )
    (net (code "12") (name "/DAC_D0") (class "Default")
      (node (ref "J3") (pin "2") (pinfunction "2_2") (pintype "passive"))
    )
    (net (code "13") (name "/DAC_D1") (class "Default")
      (node (ref "J8") (pin "2") (pinfunction "2_2") (pintype "passive"))
    )
    (net (code "14") (name "/DAC_D2") (class "Default")
      (node (ref "J10") (pin "2") (pinfunction "2_2") (pintype "passive"))
    )
    (net (code "15") (name "/DAC_D3") (class "Default")
      (node (ref "J12") (pin "2") (pinfunction "2_2") (pintype "passive"))
    )
    (net (code "16") (name "/DAC_MUTE_N") (class "Default")
      (node (ref "J7") (pin "10") (pinfunction "10_10") (pintype "passive"))
    )
    (net (code "17") (name "/EXT_PLL_SEL") (class "Default")
      (node (ref "J43") (pin "8") (pinfunction "8_8") (pintype "passive"))
    )
    (net (code "18") (name "/I2C0_SCL") (class "Default")
      (node (ref "J7") (pin "13") (pinfunction "13_13") (pintype "passive"))
      (node (ref "R127") (pin "1") (pinfunction "1_1") (pintype "passive"))
      (node (ref "R131") (pin "1") (pinfunction "1_1") (pintype "passive"))
      (node (ref "R133") (pin "2") (pinfunction "2_2") (pintype "passive"))
      (node (ref "U33") (pin "5") (pinfunction "SC0_5") (pintype "passive"))
    )
    (net (code "19") (name "/I2C0_SDA") (class "Default")
      (node (ref "J7") (pin "15") (pinfunction "15_15") (pintype "passive"))
      (node (ref "R128") (pin "1") (pinfunction "1_1") (pintype "passive"))
      (node (ref "R132") (pin "1") (pinfunction "1_1") (pintype "passive"))
      (node (ref "R134") (pin "2") (pinfunction "2_2") (pintype "passive"))
      (node (ref "U33") (pin "4") (pinfunction "SD0_4") (pintype "passive"))
    )
    (net (code "20") (name "/I2C1_SCL") (class "Default")
      (node (ref "R129") (pin "1") (pinfunction "1_1") (pintype "passive"))
      (node (ref "R133") (pin "1") (pinfunction "1_1") (pintype "passive"))
      (node (ref "U33") (pin "8") (pinfunction "SC1_8") (pintype "passive"))
    )
    (net (code "21") (name "/I2C1_SDA") (class "Default")
      (node (ref "R130") (pin "1") (pinfunction "1_1") (pintype "passive"))
      (node (ref "R134") (pin "1") (pinfunction "1_1") (pintype "passive"))
      (node (ref "U33") (pin "7") (pinfunction "SD1_7") (pintype "passive"))
    )
    (net (code "22") (name "/I2C_SCL") (class "Default")
      (node (ref "R131") (pin "2") (pinfunction "2_2") (pintype "passive"))
      (node (ref "R41") (pin "1") (pinfunction "1_1") (pintype "passive"))
      (node (ref "U33") (pin "1") (pinfunction "SCL_1") (pintype "passive"))
    )
    (net (code "23") (name "/I2C_SDA") (class "Default")
      (node (ref "R132") (pin "2") (pinfunction "2_2") (pintype "passive"))
      (node (ref "R42") (pin "1") (pinfunction "1_1") (pintype "passive"))
      (node (ref "U33") (pin "2") (pinfunction "SDA_2") (pintype "passive"))
    )
    (net (code "24") (name "/I2S_DAC_LOOP_D0") (class "Default")
      (node (ref "R24") (pin "1") (pinfunction "1_1") (pintype "passive"))
    )
    (net (code "25") (name "/I2S_DAC_LOOP_D1") (class "Default")
      (node (ref "R25") (pin "1") (pinfunction "1_1") (pintype "passive"))
    )
    (net (code "26") (name "/I2S_DAC_LOOP_D2") (class "Default")
      (node (ref "R27") (pin "1") (pinfunction "1_1") (pintype "passive"))
    )
    (net (code "27") (name "/I2S_DAC_LOOP_D3") (class "Default")
      (node (ref "R32") (pin "1") (pinfunction "1_1") (pintype "passive"))
    )
    (net (code "28") (name "/LED_0") (class "Default")
      (node (ref "R36") (pin "2") (pinfunction "2_2") (pintype "passive"))
    )
    (net (code "29") (name "/LED_1") (class "Default")
      (node (ref "R35") (pin "2") (pinfunction "2_2") (pintype "passive"))
    )
    (net (code "30") (name "/LED_2") (class "Default")
      (node (ref "R34") (pin "2") (pinfunction "2_2") (pintype "passive"))
    )
    (net (code "31") (name "/LED_3") (class "Default")
      (node (ref "R33") (pin "2") (pinfunction "2_2") (pintype "passive"))
    )
    (net (code "32") (name "/LRCK") (class "Default")
      (node (ref "J7") (pin "11") (pinfunction "11_11") (pintype "passive"))
      (node (ref "R12") (pin "2") (pinfunction "2_2") (pintype "passive"))
    )
    (net (code "34") (name "/MCLK_DAC") (class "Default")
      (node (ref "J7") (pin "1") (pinfunction "1_1") (pintype "passive"))
    )
    (net (code "35") (name "/MCLK_DIG") (class "Default")
      (node (ref "J41") (pin "7") (pinfunction "7_7") (pintype "passive"))
    )
    (net (code "36") (name "/MCLK_DIR") (class "Default")
      (node (ref "J43") (pin "6") (pinfunction "6_6") (pintype "passive"))
    )
    (net (code "37") (name "/MCLK_XMOS") (class "Default")
      (node (ref "R117") (pin "2") (pinfunction "2_2") (pintype "passive"))
    )
    (net (code "38") (name "/MCLK_X_PIN") (class "Default")
      (node (ref "R117") (pin "1") (pinfunction "1_1") (pintype "passive"))
      (node (ref "R118") (pin "1") (pinfunction "1_1") (pintype "passive"))
      (node (ref "TP27") (pin "1") (pinfunction "1_1") (pintype "passive"))
    )
    (net (code "39") (name "/MIDI_RX") (class "Default")
      (node (ref "J41") (pin "10") (pinfunction "10_10") (pintype "passive"))
    )
    (net (code "40") (name "/MIDI_TX") (class "Default")
      (node (ref "J41") (pin "9") (pinfunction "9_9") (pintype "passive"))
    )
    (net (code "41") (name "/OPT_RX") (class "Default")
      (node (ref "J41") (pin "4") (pinfunction "4_4") (pintype "passive"))
    )
    (net (code "42") (name "/OPT_TX") (class "Default")
      (node (ref "J41") (pin "3") (pinfunction "3_3") (pintype "passive"))
    )
    (net (code "43") (name "/PLL_SYNC") (class "Default")
      (node (ref "J43") (pin "2") (pinfunction "2_2") (pintype "passive"))
    )
    (net (code "44") (name "/QSPI_CLK") (class "Default")
      (node (ref "J44") (pin "7") (pinfunction "7_7") (pintype "passive"))
      (node (ref "U9") (pin "6") (pinfunction "SCK_6") (pintype "input"))
    )
    (net (code "45") (name "/QSPI_CS_N") (class "Default")
      (node (ref "J44") (pin "9") (pinfunction "9_9") (pintype "passive"))
      (node (ref "R38") (pin "1") (pinfunction "1_1") (pintype "passive"))
      (node (ref "U9") (pin "1") (pinfunction "CS_N_1") (pintype "input"))
    )
    (net (code "46") (name "/QSPI_D0") (class "Default")
      (node (ref "J44") (pin "3") (pinfunction "3_3") (pintype "passive"))
      (node (ref "U9") (pin "5") (pinfunction "SI/IO0_5") (pintype "bidirectional"))
    )
    (net (code "47") (name "/QSPI_D1") (class "Default")
      (node (ref "J44") (pin "4") (pinfunction "4_4") (pintype "passive"))
      (node (ref "U9") (pin "2") (pinfunction "SO/IO1_2") (pintype "bidirectional"))
    )
    (net (code "48") (name "/QSPI_D2") (class "Default")
      (node (ref "J44") (pin "5") (pinfunction "5_5") (pintype "passive"))
      (node (ref "U9") (pin "3") (pinfunction "WP_N/IO2_3") (pintype "bidirectional"))
    )
    (net (code "49") (name "/QSPI_D3") (class "Default")
      (node (ref "J44") (pin "6") (pinfunction "6_6") (pintype "passive"))
      (node (ref "U9") (pin "7") (pinfunction "HOLD_N/IO3_7") (pintype "bidirectional"))
    )
    (net (code "50") (name "/RST_N") (class "Default")
      (node (ref "C177") (pin "1") (pinfunction "1_1") (pintype "passive"))
      (node (ref "J4") (pin "10") (pinfunction "10_10") (pintype "passive"))
      (node (ref "J45") (pin "10") (pinfunction "10_10") (pintype "passive"))
      (node (ref "R43") (pin "1") (pinfunction "1_1") (pintype "passive"))
    )
    (net (code "51") (name "/SUSPEND_N") (class "Default")
      (node (ref "J43") (pin "5") (pinfunction "5_5") (pintype "passive"))
    )
    (net (code "52") (name "/TCK") (class "Default")
      (node (ref "J4") (pin "4") (pinfunction "4_4") (pintype "passive"))
      (node (ref "J45") (pin "4") (pinfunction "4_4") (pintype "passive"))
    )
    (net (code "53") (name "/TDI") (class "Default")
      (node (ref "J4") (pin "8") (pinfunction "8_8") (pintype "passive"))
    )
    (net (code "54") (name "/TDO") (class "Default")
      (node (ref "J4") (pin "6") (pinfunction "6_6") (pintype "passive"))
      (node (ref "R123") (pin "2") (pinfunction "2_2") (pintype "passive"))
      (node (ref "R124") (pin "1") (pinfunction "1_1") (pintype "passive"))
    )
    (net (code "55") (name "/TDO_1") (class "Default")
      (node (ref "R122") (pin "2") (pinfunction "2_2") (pintype "passive"))
    )
    (net (code "56") (name "/TDO_EXT") (class "Default")
      (node (ref "J45") (pin "6") (pinfunction "6_6") (pintype "passive"))
      (node (ref "R124") (pin "2") (pinfunction "2_2") (pintype "passive"))
    )
    (net (code "57") (name "/TDO_X") (class "Default")
      (node (ref "J45") (pin "8") (pinfunction "8_8") (pintype "passive"))
      (node (ref "R122") (pin "1") (pinfunction "1_1") (pintype "passive"))
      (node (ref "R123") (pin "1") (pinfunction "1_1") (pintype "passive"))
    )
    (net (code "58") (name "/TMS") (class "Default")
      (node (ref "J4") (pin "2") (pinfunction "2_2") (pintype "passive"))
      (node (ref "J45") (pin "2") (pinfunction "2_2") (pintype "passive"))
    )
    (net (code "59") (name "/USB_D_N") (class "Default")
      (node (ref "D8") (pin "6") (pinfunction "6_6") (pintype "passive"))
      (node (ref "J16") (pin "2") (pinfunction "DM_2") (pintype "passive"))
    )
    (net (code "60") (name "/USB_D_P") (class "Default")
      (node (ref "D8") (pin "1") (pinfunction "1_1") (pintype "passive"))
      (node (ref "J16") (pin "3") (pinfunction "DP_3") (pintype "passive"))
    )
    (net (code "61") (name "/VBUS") (class "Default")
      (node (ref "C63") (pin "1") (pinfunction "1_1") (pintype "passive"))
      (node (ref "D8") (pin "5") (pinfunction "5_5") (pintype "passive"))
      (node (ref "J14") (pin "1") (pinfunction "1_1") (pintype "passive"))
      (node (ref "J15") (pin "1") (pinfunction "1_1") (pintype "passive"))
      (node (ref "J16") (pin "1") (pinfunction "VBUS_1") (pintype "passive"))
      (node (ref "R47") (pin "1") (pinfunction "1_1") (pintype "passive"))
    )
    (net (code "62") (name "/VBUS_DETECT") (class "Default")
      (node (ref "J43") (pin "3") (pinfunction "3_3") (pintype "passive"))
      (node (ref "Q1") (pin "3") (pinfunction "C1_3") (pintype "passive"))
      (node (ref "R44") (pin "1") (pinfunction "1_1") (pintype "passive"))
    )
    (net (code "63") (name "/WCLK_IN") (class "Default")
      (node (ref "J43") (pin "10") (pinfunction "10_10") (pintype "passive"))
    )
    (net (code "64") (name "/X0D11") (class "Default")
      (node (ref "R118") (pin "2") (pinfunction "2_2") (pintype "passive"))
    )
    (net (code "65") (name "/X0D12") (class "Default")
      (node (ref "J1") (pin "3") (pinfunction "3_3") (pintype "passive"))
    )
    (net (code "66") (name "/X0D13") (class "Default")
      (node (ref "J1") (pin "4") (pinfunction "4_4") (pintype "passive"))
    )
    (net (code "67") (name "/X0D22") (class "Default")
      (node (ref "J1") (pin "5") (pinfunction "5_5") (pintype "passive"))
    )
    (net (code "68") (name "/X0D23") (class "Default")
      (node (ref "J1") (pin "6") (pinfunction "6_6") (pintype "passive"))
    )
    (net (code "69") (name "/X0D24") (class "Default")
      (node (ref "J37") (pin "9") (pinfunction "9_9") (pintype "passive"))
    )
    (net (code "70") (name "/X0D25") (class "Default")
      (node (ref "J37") (pin "10") (pinfunction "10_10") (pintype "passive"))
    )
    (net (code "71") (name "/X0D34") (class "Default")
      (node (ref "J43") (pin "1") (pinfunction "1_1") (pintype "passive"))
    )
    (net (code "72") (name "/X0D40") (class "Default")
      (node (ref "J43") (pin "9") (pinfunction "9_9") (pintype "passive"))
    )
    (net (code "73") (name "/X1D01") (class "Default")
      (node (ref "R12") (pin "1") (pinfunction "1_1") (pintype "passive"))
    )
    (net (code "74") (name "/X1D09") (class "Default")
      (node (ref "TP32") (pin "1") (pinfunction "1_1") (pintype "passive"))
    )
    (net (code "75") (name "/X1D10") (class "Default")
      (node (ref "R13") (pin "1") (pinfunction "1_1") (pintype "passive"))
    )
    (net (code "76") (name "/X1D12") (class "Default")
      (node (ref "J1") (pin "7") (pinfunction "7_7") (pintype "passive"))
    )
    (net (code "77") (name "/X1D15") (class "Default")
      (node (ref "J37") (pin "3") (pinfunction "3_3") (pintype "passive"))
    )
    (net (code "78") (name "/X1D18") (class "Default")
      (node (ref "R39") (pin "1") (pinfunction "1_1") (pintype "passive"))
    )
    (net (code "79") (name "/X1D19") (class "Default")
      (node (ref "R40") (pin "1") (pinfunction "1_1") (pintype "passive"))
    )
    (net (code "80") (name "/X1D20") (class "Default")
      (node (ref "J37") (pin "4") (pinfunction "4_4") (pintype "passive"))
    )
    (net (code "81") (name "/X1D21") (class "Default")
      (node (ref "J37") (pin "5") (pinfunction "5_5") (pintype "passive"))
    )
    (net (code "82") (name "/X1D23") (class "Default")
      (node (ref "J1") (pin "9") (pinfunction "9_9") (pintype "passive"))
    )
    (net (code "83") (name "/X1D26") (class "Default")
      (node (ref "J42") (pin "1") (pinfunction "1_1") (pintype "passive"))
    )
    (net (code "84") (name "/X1D27") (class "Default")
      (node (ref "J42") (pin "2") (pinfunction "2_2") (pintype "passive"))
    )
    (net (code "85") (name "/X1D28") (class "Default")
      (node (ref "J42") (pin "3") (pinfunction "3_3") (pintype "passive"))
    )
    (net (code "86") (name "/X1D29") (class "Default")
      (node (ref "J42") (pin "5") (pinfunction "5_5") (pintype "passive"))
    )
    (net (code "87") (name "/X1D30") (class "Default")
      (node (ref "J42") (pin "6") (pinfunction "6_6") (pintype "passive"))
    )
    (net (code "88") (name "/X1D31") (class "Default")
      (node (ref "J42") (pin "8") (pinfunction "8_8") (pintype "passive"))
    )
    (net (code "89") (name "/X1D32") (class "Default")
      (node (ref "J42") (pin "9") (pinfunction "9_9") (pintype "passive"))
    )
    (net (code "90") (name "/X1D33") (class "Default")
      (node (ref "J42") (pin "10") (pinfunction "10_10") (pintype "passive"))
    )
    (net (code "91") (name "/X1D43") (class "Default")
      (node (ref "J37") (pin "6") (pinfunction "6_6") (pintype "passive"))
    )
    (net (code "92") (name "/X1D49") (class "Default")
      (node (ref "J38") (pin "2") (pinfunction "2_2") (pintype "passive"))
    )
    (net (code "93") (name "/X1D50") (class "Default")
      (node (ref "J38") (pin "3") (pinfunction "3_3") (pintype "passive"))
    )
    (net (code "94") (name "/X1D51") (class "Default")
      (node (ref "J38") (pin "5") (pinfunction "5_5") (pintype "passive"))
    )
    (net (code "95") (name "/X1D52") (class "Default")
      (node (ref "J38") (pin "6") (pinfunction "6_6") (pintype "passive"))
    )
    (net (code "96") (name "/X1D53") (class "Default")
      (node (ref "J38") (pin "7") (pinfunction "7_7") (pintype "passive"))
    )
    (net (code "97") (name "/X1D54") (class "Default")
      (node (ref "J38") (pin "10") (pinfunction "10_10") (pintype "passive"))
    )
    (net (code "98") (name "/X1D55") (class "Default")
      (node (ref "J38") (pin "11") (pinfunction "11_11") (pintype "passive"))
    )
    (net (code "99") (name "/X1D56") (class "Default")
      (node (ref "J38") (pin "12") (pinfunction "12_12") (pintype "passive"))
    )
    (net (code "100") (name "/X1D57") (class "Default")
      (node (ref "J38") (pin "14") (pinfunction "14_14") (pintype "passive"))
    )
    (net (code "101") (name "/X1D58") (class "Default")
      (node (ref "J38") (pin "15") (pinfunction "15_15") (pintype "passive"))
    )
    (net (code "102") (name "/XL_DN0") (class "Default")
      (node (ref "J4") (pin "14") (pinfunction "14_14") (pintype "passive"))
    )
    (net (code "103") (name "/XL_DN1") (class "Default")
      (node (ref "J4") (pin "12") (pinfunction "12_12") (pintype "passive"))
    )
    (net (code "104") (name "/XL_UP0") (class "Default")
      (node (ref "J4") (pin "16") (pinfunction "16_16") (pintype "passive"))
      (node (ref "R39") (pin "2") (pinfunction "2_2") (pintype "passive"))
    )
    (net (code "105") (name "/XL_UP1") (class "Default")
      (node (ref "J4") (pin "18") (pinfunction "18_18") (pintype "passive"))
      (node (ref "R40") (pin "2") (pinfunction "2_2") (pintype "passive"))
    )
    (net (code "106") (name "/X_ADC_D0") (class "Default")
      (node (ref "J6") (pin "3") (pinfunction "3_3") (pintype "passive"))
      (node (ref "J7") (pin "19") (pinfunction "19_19") (pintype "passive"))
    )
    (net (code "107") (name "/X_ADC_D1") (class "Default")
      (node (ref "J7") (pin "18") (pinfunction "18_18") (pintype "passive"))
      (node (ref "J9") (pin "3") (pinfunction "3_3") (pintype "passive"))
    )
    (net (code "108") (name "/X_ADC_D2") (class "Default")
      (node (ref "J11") (pin "3") (pinfunction "3_3") (pintype "passive"))
      (node (ref "J7") (pin "17") (pinfunction "17_17") (pintype "passive"))
    )
    (net (code "109") (name "/X_ADC_D3") (class "Default")
      (node (ref "J13") (pin "3") (pinfunction "3_3") (pintype "passive"))
      (node (ref "J7") (pin "16") (pinfunction "16_16") (pintype "passive"))
    )
    (net (code "110") (name "/X_DAC_D0") (class "Default")
      (node (ref "J3") (pin "3") (pinfunction "3_3") (pintype "passive"))
      (node (ref "J7") (pin "3") (pinfunction "3_3") (pintype "passive"))
    )
    (net (code "111") (name "/X_DAC_D1") (class "Default")
      (node (ref "J7") (pin "4") (pinfunction "4_4") (pintype "passive"))
      (node (ref "J8") (pin "3") (pinfunction "3_3") (pintype "passive"))
    )
    (net (code "112") (name "/X_DAC_D2") (class "Default")
      (node (ref "J10") (pin "3") (pinfunction "3_3") (pintype "passive"))
      (node (ref "J7") (pin "5") (pinfunction "5_5") (pintype "passive"))
    )
    (net (code "113") (name "/X_DAC_D3") (class "Default")
      (node (ref "J12") (pin "3") (pinfunction "3_3") (pintype "passive"))
      (node (ref "J7") (pin "6") (pinfunction "6_6") (pintype "passive"))
    )
    (net (code "114") (name "1V8") (class "Default")
      (node (ref "C164") (pin "1") (pinfunction "1_1") (pintype "passive"))
      (node (ref "J1") (pin "1") (pinfunction "1_1") (pintype "passive"))
      (node (ref "J4") (pin "1") (pinfunction "1_1") (pintype "passive"))
      (node (ref "R43") (pin "2") (pinfunction "2_2") (pintype "passive"))
    )
    (net (code "115") (name "3V3") (class "Default")
      (node (ref "C175") (pin "1") (pinfunction "1_1") (pintype "passive"))
      (node (ref "J37") (pin "1") (pinfunction "1_1") (pintype "passive"))
      (node (ref "J41") (pin "1") (pinfunction "1_1") (pintype "passive"))
      (node (ref "J7") (pin "7") (pinfunction "7_7") (pintype "passive"))
      (node (ref "R119") (pin "2") (pinfunction "2_2") (pintype "passive"))
      (node (ref "R127") (pin "2") (pinfunction "2_2") (pintype "passive"))
      (node (ref "R128") (pin "2") (pinfunction "2_2") (pintype "passive"))
      (node (ref "R129") (pin "2") (pinfunction "2_2") (pintype "passive"))
      (node (ref "R130") (pin "2") (pinfunction "2_2") (pintype "passive"))
      (node (ref "R23") (pin "2") (pinfunction "2_2") (pintype "passive"))
      (node (ref "R37") (pin "2") (pinfunction "2_2") (pintype "passive"))
      (node (ref "R41") (pin "2") (pinfunction "2_2") (pintype "passive"))
      (node (ref "R42") (pin "2") (pinfunction "2_2") (pintype "passive"))
      (node (ref "U33") (pin "3") (pinfunction "VDD_3") (pintype "power_in"))
    )
    (net (code "116") (name "3V3X") (class "Default")
      (node (ref "C165") (pin "1") (pinfunction "1_1") (pintype "passive"))
      (node (ref "C62") (pin "1") (pinfunction "1_1") (pintype "passive"))
      (node (ref "J4") (pin "11") (pinfunction "11_11") (pintype "passive"))
      (node (ref "J44") (pin "1") (pinfunction "1_1") (pintype "passive"))
      (node (ref "R38") (pin "2") (pinfunction "2_2") (pintype "passive"))
      (node (ref "R44") (pin "2") (pinfunction "2_2") (pintype "passive"))
      (node (ref "U9") (pin "8") (pinfunction "VCC_8") (pintype "power_in"))
    )
    (net (code "117") (name "GND") (class "Default")
      (node (ref "C164") (pin "2") (pinfunction "2_2") (pintype "passive"))
      (node (ref "C165") (pin "2") (pinfunction "2_2") (pintype "passive"))
      (node (ref "C175") (pin "2") (pinfunction "2_2") (pintype "passive"))
      (node (ref "C177") (pin "2") (pinfunction "2_2") (pintype "passive"))
      (node (ref "C62") (pin "2") (pinfunction "2_2") (pintype "passive"))
      (node (ref "C63") (pin "2") (pinfunction "2_2") (pintype "passive"))
      (node (ref "C64") (pin "2") (pinfunction "2_2") (pintype "passive"))
      (node (ref "D4") (pin "1") (pinfunction "K_1") (pintype "passive"))
      (node (ref "D5") (pin "1") (pinfunction "K_1") (pintype "passive"))
      (node (ref "D6") (pin "1") (pinfunction "K_1") (pintype "passive"))
      (node (ref "D7") (pin "1") (pinfunction "K_1") (pintype "passive"))
      (node (ref "D8") (pin "2") (pinfunction "2_2") (pintype "passive"))
      (node (ref "J1") (pin "2") (pinfunction "2_2") (pintype "passive"))
      (node (ref "J1") (pin "8") (pinfunction "8_8") (pintype "passive"))
      (node (ref "J16") (pin "5") (pinfunction "GND_5") (pintype "passive"))
      (node (ref "J16") (pin "S1") (pinfunction "S1_S1") (pintype "passive"))
      (node (ref "J16") (pin "S2") (pinfunction "S2_S2") (pintype "passive"))
      (node (ref "J16") (pin "S3") (pinfunction "S3_S3") (pintype "passive"))
      (node (ref "J16") (pin "S4") (pinfunction "S4_S4") (pintype "passive"))
      (node (ref "J16") (pin "S5") (pinfunction "S5_S5") (pintype "passive"))
      (node (ref "J16") (pin "S6") (pinfunction "S6_S6") (pintype "passive"))
      (node (ref "J17") (pin "1") (pinfunction "1_1") (pintype "passive"))
      (node (ref "J17") (pin "2") (pinfunction "2_2") (pintype "passive"))
      (node (ref "J37") (pin "2") (pinfunction "2_2") (pintype "passive"))
      (node (ref "J37") (pin "8") (pinfunction "8_8") (pintype "passive"))
      (node (ref "J38") (pin "1") (pinfunction "1_1") (pintype "passive"))
      (node (ref "J38") (pin "13") (pinfunction "13_13") (pintype "passive"))
      (node (ref "J38") (pin "16") (pinfunction "16_16") (pintype "passive"))
      (node (ref "J38") (pin "4") (pinfunction "4_4") (pintype "passive"))
      (node (ref "J38") (pin "8") (pinfunction "8_8") (pintype "passive"))
      (node (ref "J38") (pin "9") (pinfunction "9_9") (pintype "passive"))
      (node (ref "J39") (pin "1") (pinfunction "1_1") (pintype "passive"))
      (node (ref "J39") (pin "2") (pinfunction "2_2") (pintype "passive"))
      (node (ref "J4") (pin "13") (pinfunction "13_13") (pintype "passive"))
      (node (ref "J4") (pin "15") (pinfunction "15_15") (pintype "passive"))
      (node (ref "J4") (pin "17") (pinfunction "17_17") (pintype "passive"))
      (node (ref "J4") (pin "19") (pinfunction "19_19") (pintype "passive"))
      (node (ref "J4") (pin "3") (pinfunction "3_3") (pintype "passive"))
      (node (ref "J4") (pin "5") (pinfunction "5_5") (pintype "passive"))
      (node (ref "J4") (pin "7") (pinfunction "7_7") (pintype "passive"))
      (node (ref "J4") (pin "9") (pinfunction "9_9") (pintype "passive"))
      (node (ref "J40") (pin "1") (pinfunction "1_1") (pintype "passive"))
      (node (ref "J40") (pin "2") (pinfunction "2_2") (pintype "passive"))
      (node (ref "J41") (pin "2") (pinfunction "2_2") (pintype "passive"))
      (node (ref "J41") (pin "8") (pinfunction "8_8") (pintype "passive"))
      (node (ref "J42") (pin "4") (pinfunction "4_4") (pintype "passive"))
      (node (ref "J42") (pin "7") (pinfunction "7_7") (pintype "passive"))
      (node (ref "J43") (pin "4") (pinfunction "4_4") (pintype "passive"))
      (node (ref "J43") (pin "7") (pinfunction "7_7") (pintype "passive"))
      (node (ref "J44") (pin "2") (pinfunction "2_2") (pintype "passive"))
      (node (ref "J44") (pin "8") (pinfunction "8_8") (pintype "passive"))
      (node (ref "J45") (pin "13") (pinfunction "13_13") (pintype "passive"))
      (node (ref "J45") (pin "15") (pinfunction "15_15") (pintype "passive"))
      (node (ref "J45") (pin "17") (pinfunction "17_17") (pintype "passive"))
      (node (ref "J45") (pin "19") (pinfunction "19_19") (pintype "passive"))
      (node (ref "J45") (pin "3") (pinfunction "3_3") (pintype "passive"))
      (node (ref "J45") (pin "5") (pinfunction "5_5") (pintype "passive"))
      (node (ref "J45") (pin "7") (pinfunction "7_7") (pintype "passive"))
      (node (ref "J45") (pin "9") (pinfunction "9_9") (pintype "passive"))
      (node (ref "J7") (pin "14") (pinfunction "14_14") (pintype "passive"))
      (node (ref "J7") (pin "2") (pinfunction "2_2") (pintype "passive"))
      (node (ref "J7") (pin "20") (pinfunction "20_20") (pintype "passive"))
      (node (ref "J7") (pin "8") (pinfunction "8_8") (pintype "passive"))
      (node (ref "Q1") (pin "2") (pinfunction "E1_2") (pintype "passive"))
      (node (ref "R46") (pin "1") (pinfunction "1_1") (pintype "passive"))
      (node (ref "R48") (pin "1") (pinfunction "1_1") (pintype "passive"))
      (node (ref "SW1") (pin "2A") (pinfunction "2A_2A") (pintype "passive"))
      (node (ref "SW1") (pin "2B") (pinfunction "2B_2B") (pintype "passive"))
      (node (ref "SW2") (pin "2A") (pinfunction "2A_2A") (pintype "passive"))
      (node (ref "SW2") (pin "2B") (pinfunction "2B_2B") (pintype "passive"))
      (node (ref "SW3") (pin "2A") (pinfunction "2A_2A") (pintype "passive"))
      (node (ref "SW3") (pin "2B") (pinfunction "2B_2B") (pintype "passive"))
      (node (ref "U33") (pin "6") (pinfunction "VSS_6") (pintype "power_in"))
      (node (ref "U9") (pin "4") (pinfunction "GND_4") (pintype "power_in"))
    )
    (net (code "118") (name "Net-(D4-A)") (class "Default")
      (node (ref "D4") (pin "2") (pinfunction "A_2") (pintype "passive"))
      (node (ref "R33") (pin "1") (pinfunction "1_1") (pintype "passive"))
    )
    (net (code "119") (name "Net-(D5-A)") (class "Default")
      (node (ref "D5") (pin "2") (pinfunction "A_2") (pintype "passive"))
      (node (ref "R34") (pin "1") (pinfunction "1_1") (pintype "passive"))
    )
    (net (code "120") (name "Net-(D6-A)") (class "Default")
      (node (ref "D6") (pin "2") (pinfunction "A_2") (pintype "passive"))
      (node (ref "R35") (pin "1") (pinfunction "1_1") (pintype "passive"))
    )
    (net (code "121") (name "Net-(D7-A)") (class "Default")
      (node (ref "D7") (pin "2") (pinfunction "A_2") (pintype "passive"))
      (node (ref "R36") (pin "1") (pinfunction "1_1") (pintype "passive"))
    )
    (net (code "122") (name "Net-(J10-Pad1)") (class "Default")
      (node (ref "J10") (pin "1") (pinfunction "1_1") (pintype "passive"))
      (node (ref "J10") (pin "4") (pinfunction "4_4") (pintype "passive"))
      (node (ref "J12") (pin "1") (pinfunction "1_1") (pintype "passive"))
      (node (ref "J12") (pin "4") (pinfunction "4_4") (pintype "passive"))
      (node (ref "J3") (pin "1") (pinfunction "1_1") (pintype "passive"))
      (node (ref "J3") (pin "4") (pinfunction "4_4") (pintype "passive"))
      (node (ref "J8") (pin "1") (pinfunction "1_1") (pintype "passive"))
      (node (ref "J8") (pin "4") (pinfunction "4_4") (pintype "passive"))
    )
    (net (code "123") (name "Net-(J11-Pad1)") (class "Default")
      (node (ref "J11") (pin "1") (pinfunction "1_1") (pintype "passive"))
      (node (ref "J11") (pin "4") (pinfunction "4_4") (pintype "passive"))
      (node (ref "J13") (pin "1") (pinfunction "1_1") (pintype "passive"))
      (node (ref "J13") (pin "4") (pinfunction "4_4") (pintype "passive"))
      (node (ref "J6") (pin "1") (pinfunction "1_1") (pintype "passive"))
      (node (ref "J6") (pin "4") (pinfunction "4_4") (pintype "passive"))
      (node (ref "J9") (pin "1") (pinfunction "1_1") (pintype "passive"))
      (node (ref "J9") (pin "4") (pinfunction "4_4") (pintype "passive"))
    )
    (net (code "124") (name "Net-(J14-Pad2)") (class "Default")
      (node (ref "J14") (pin "2") (pinfunction "2_2") (pintype "passive"))
      (node (ref "R45") (pin "1") (pinfunction "1_1") (pintype "passive"))
      (node (ref "R46") (pin "2") (pinfunction "2_2") (pintype "passive"))
    )
    (net (code "125") (name "Net-(Q1-B1)") (class "Default")
      (node (ref "Q1") (pin "1") (pinfunction "B1_1") (pintype "passive"))
      (node (ref "R45") (pin "2") (pinfunction "2_2") (pintype "passive"))
    )
    (net (code "126") (name "USB_VBUS") (class "Default")
      (node (ref "C64") (pin "1") (pinfunction "1_1") (pintype "passive"))
      (node (ref "J15") (pin "2") (pinfunction "2_2") (pintype "passive"))
      (node (ref "R47") (pin "2") (pinfunction "2_2") (pintype "passive"))
      (node (ref "R48") (pin "2") (pinfunction "2_2") (pintype "passive"))
    )
    (net (code "127") (name "unconnected-(D8-Pad3)") (class "Default")
      (node (ref "D8") (pin "3") (pinfunction "3_3") (pintype "passive+no_connect"))
    )
    (net (code "128") (name "unconnected-(D8-Pad4)") (class "Default")
      (node (ref "D8") (pin "4") (pinfunction "4_4") (pintype "passive+no_connect"))
    )
    (net (code "129") (name "unconnected-(J1-Pad10)") (class "Default")
      (node (ref "J1") (pin "10") (pinfunction "10_10") (pintype "passive+no_connect"))
    )
    (net (code "130") (name "unconnected-(J4-Pad20)") (class "Default")
      (node (ref "J4") (pin "20") (pinfunction "20_20") (pintype "passive+no_connect"))
    )
    (net (code "131") (name "unconnected-(J16-ID-Pad4)") (class "Default")
      (node (ref "J16") (pin "4") (pinfunction "ID_4") (pintype "passive+no_connect"))
    )
    (net (code "132") (name "unconnected-(J37-Pad7)") (class "Default")
      (node (ref "J37") (pin "7") (pinfunction "7_7") (pintype "passive+no_connect"))
    )
    (net (code "133") (name "unconnected-(J44-Pad10)") (class "Default")
      (node (ref "J44") (pin "10") (pinfunction "10_10") (pintype "passive+no_connect"))
    )
    (net (code "134") (name "unconnected-(J45-Pad1)") (class "Default")
      (node (ref "J45") (pin "1") (pinfunction "1_1") (pintype "passive+no_connect"))
    )
    (net (code "135") (name "unconnected-(J45-Pad11)") (class "Default")
      (node (ref "J45") (pin "11") (pinfunction "11_11") (pintype "passive+no_connect"))
    )
    (net (code "136") (name "unconnected-(J45-Pad12)") (class "Default")
      (node (ref "J45") (pin "12") (pinfunction "12_12") (pintype "passive+no_connect"))
    )
    (net (code "137") (name "unconnected-(J45-Pad14)") (class "Default")
      (node (ref "J45") (pin "14") (pinfunction "14_14") (pintype "passive+no_connect"))
    )
    (net (code "138") (name "unconnected-(J45-Pad16)") (class "Default")
      (node (ref "J45") (pin "16") (pinfunction "16_16") (pintype "passive+no_connect"))
    )
    (net (code "139") (name "unconnected-(J45-Pad18)") (class "Default")
      (node (ref "J45") (pin "18") (pinfunction "18_18") (pintype "passive+no_connect"))
    )
    (net (code "140") (name "unconnected-(J45-Pad20)") (class "Default")
      (node (ref "J45") (pin "20") (pinfunction "20_20") (pintype "passive+no_connect"))
    )
    (net (code "141") (name "unconnected-(SW1-Pad1B)") (class "Default")
      (node (ref "SW1") (pin "1B") (pinfunction "1B_1B") (pintype "passive+no_connect"))
    )
    (net (code "142") (name "unconnected-(SW2-Pad1B)") (class "Default")
      (node (ref "SW2") (pin "1B") (pinfunction "1B_1B") (pintype "passive+no_connect"))
    )
    (net (code "143") (name "unconnected-(SW3-Pad1B)") (class "Default")
      (node (ref "SW3") (pin "1B") (pinfunction "1B_1B") (pintype "passive+no_connect"))
    )
  )
)
